# R4_Odzyskowa.net
KiCad netlist of a schematic drawn in EasyEDA
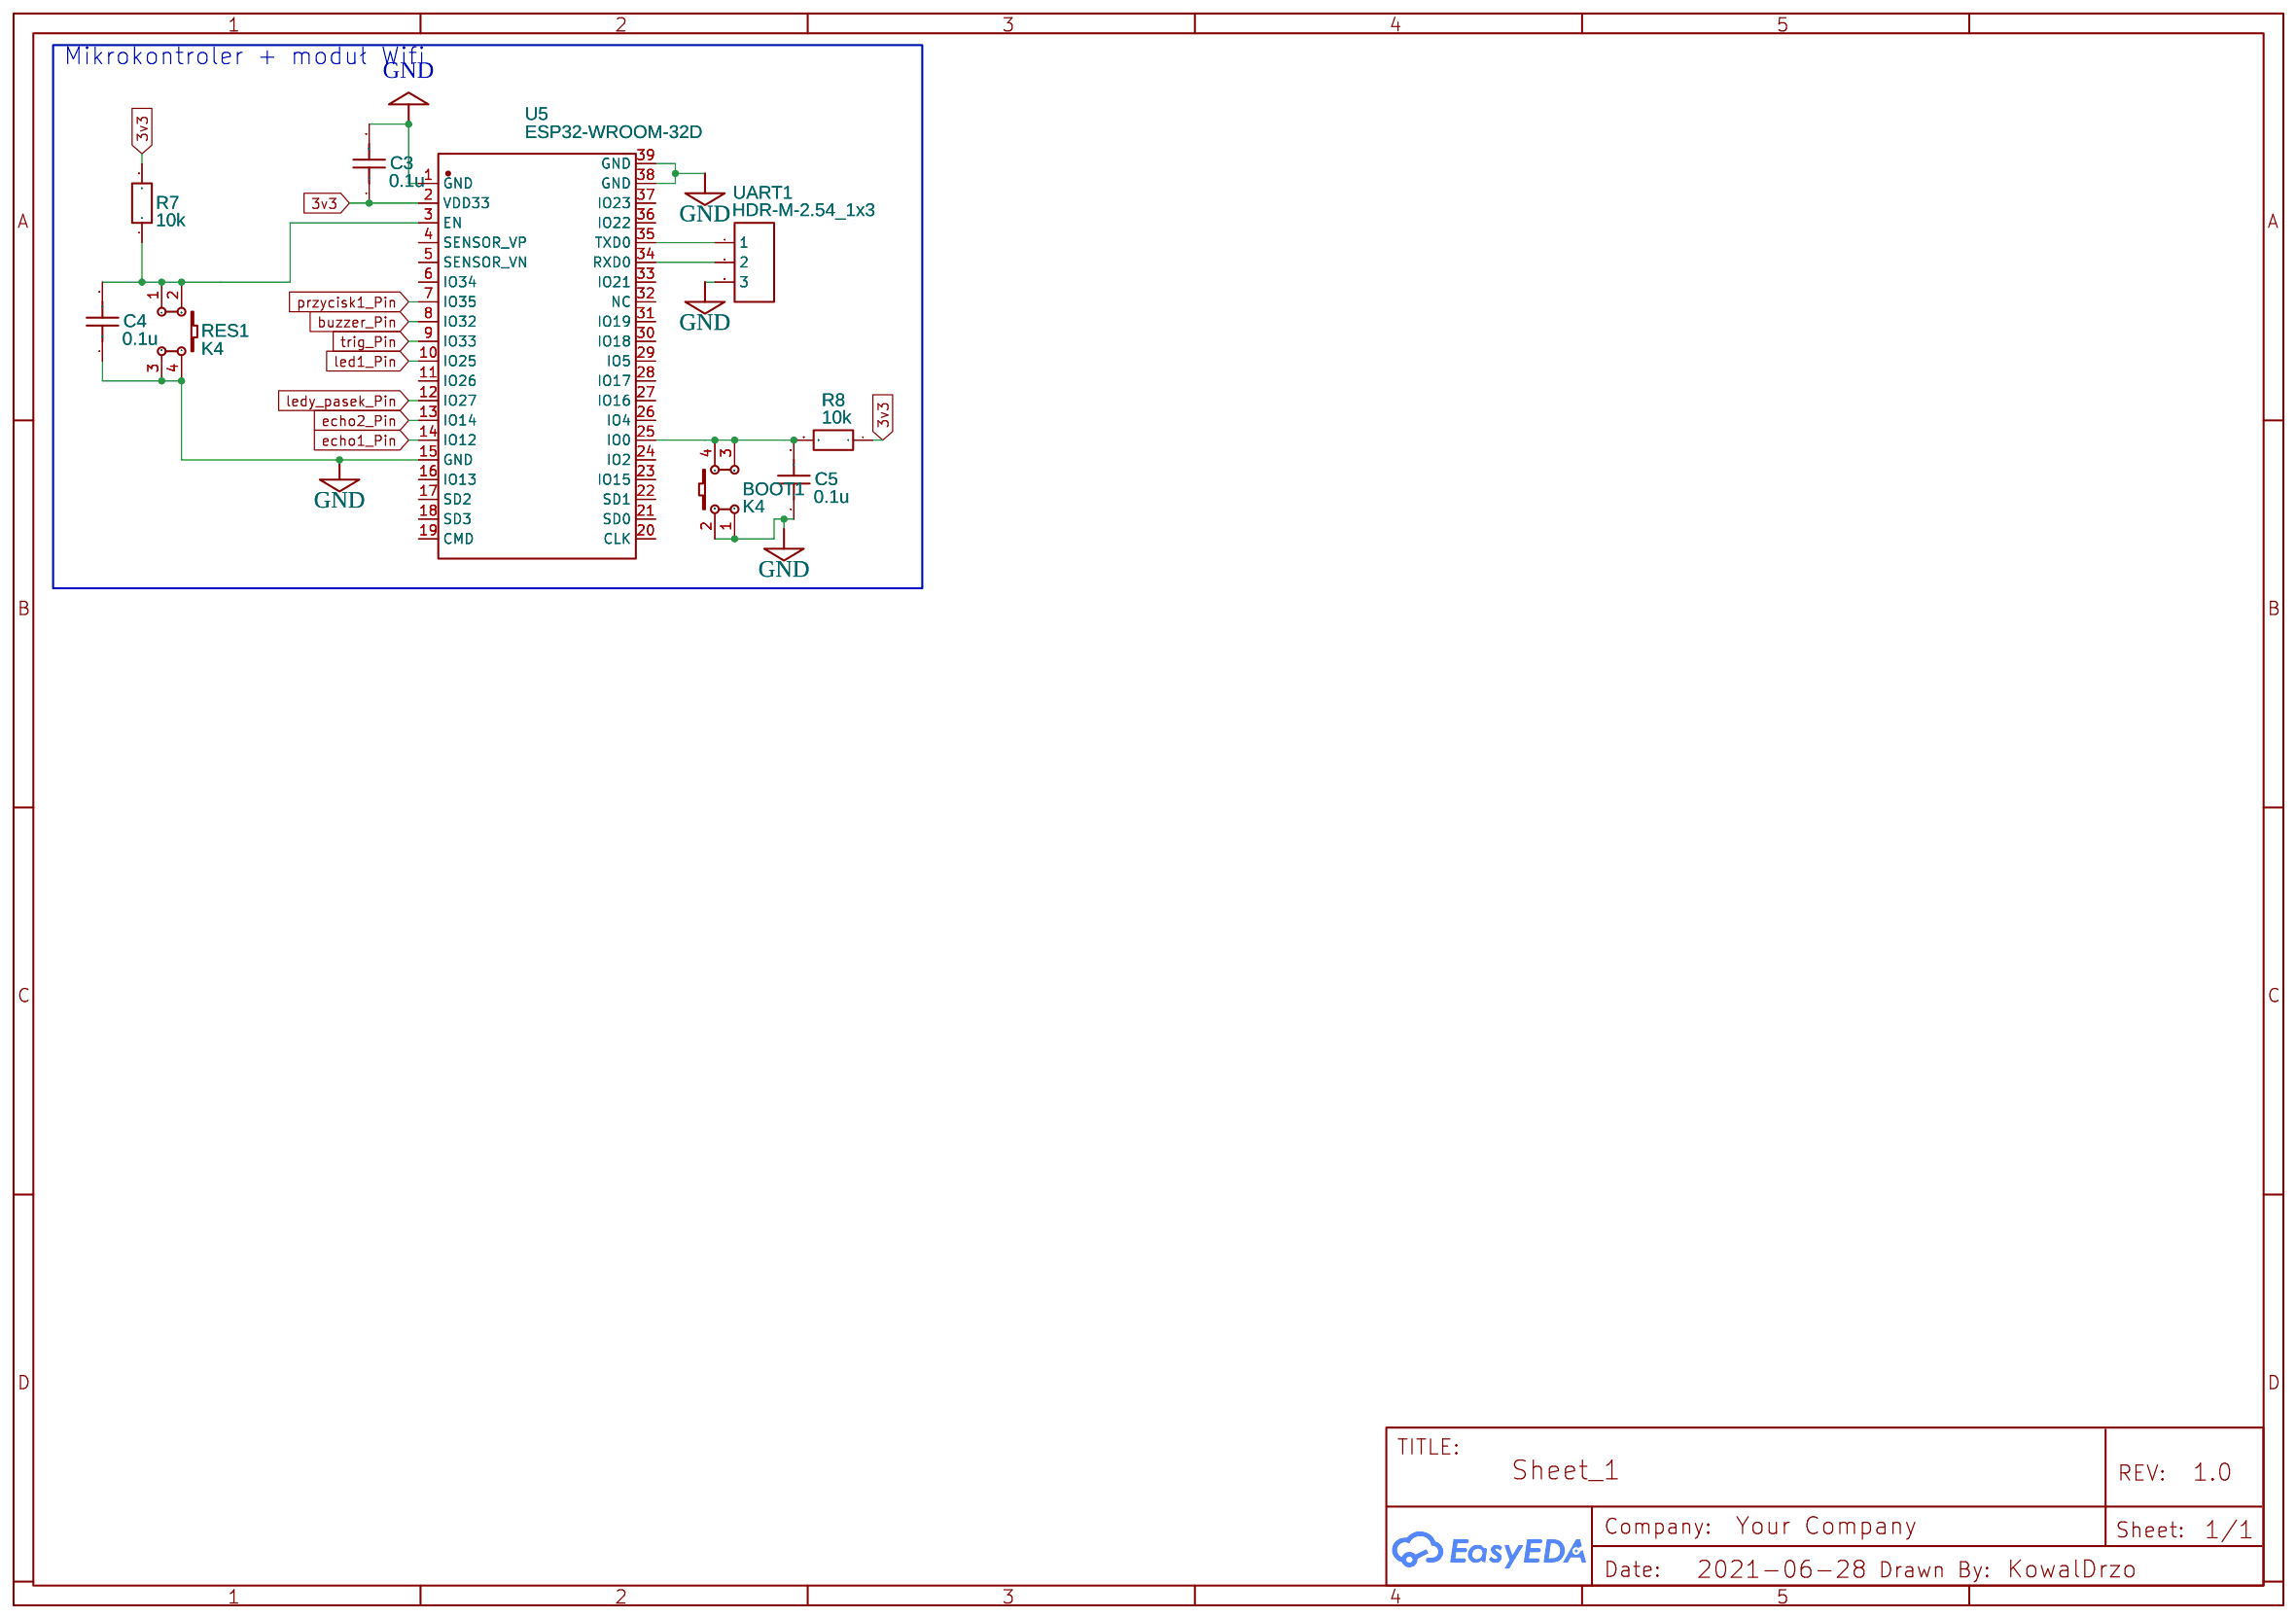
[diagram p0: schematic sheet]

(export (version "E")
  (design (tool "Eeschema 10.0.6"))
  (components
    (comp (ref "BOOT1")
      (value "K4")
      (fields
        (field (name "BOM_Manufacturer Part") "K2-1102DP-E4SW-04")
        (field (name "BOM_Supplier Part") "C136684")
      )
      (libsource (lib "") (part "K4-6×6_TH"))
    )
    (comp (ref "C3") (value "0.1u") (libsource (lib "") (part "C_0805_US")))
    (comp (ref "C4") (value "0.1u") (libsource (lib "") (part "C_0805_US")))
    (comp (ref "C5") (value "0.1u") (libsource (lib "") (part "C_0805_US")))
    (comp (ref "R7") (value "10k") (libsource (lib "") (part "R_0805_EU")))
    (comp (ref "R8") (value "10k") (libsource (lib "") (part "R_0805_EU_1")))
    (comp (ref "RES1")
      (value "K4")
      (fields
        (field (name "BOM_Manufacturer Part") "K2-1102DP-E4SW-04")
        (field (name "BOM_Supplier Part") "C136684")
      )
      (libsource (lib "") (part "K4-6×6_TH_1"))
    )
    (comp (ref "U5")
      (value "ESP32-WROOM-32D")
      (fields (field (name "BOM_Supplier Part") "C473012"))
      (libsource (lib "") (part "ESP32-WROOM-32D"))
    )
    (comp (ref "UART1")
      (value "HDR-M-2.54_1x3")
      (fields (field (name "BOM_Supplier Part") "C180248"))
      (libsource (lib "") (part "HDR-M-2.54_1x3"))
    )
  )
  (nets
    (net (code "1") (name "3v3") (class "Default")
      (node (ref "C3") (pin "1") (pinfunction "1_1") (pintype "unspecified"))
      (node (ref "R7") (pin "2") (pinfunction "2_2") (pintype "unspecified"))
      (node (ref "R8") (pin "1") (pinfunction "1_1") (pintype "unspecified"))
      (node (ref "U5") (pin "2") (pinfunction "VDD33_2") (pintype "unspecified"))
    )
    (net (code "2") (name "GND") (class "Default")
      (node (ref "BOOT1") (pin "1") (pinfunction "1_1") (pintype "unspecified"))
      (node (ref "BOOT1") (pin "2") (pinfunction "2_2") (pintype "unspecified"))
      (node (ref "C3") (pin "2") (pinfunction "2_2") (pintype "unspecified"))
      (node (ref "C4") (pin "1") (pinfunction "1_1") (pintype "unspecified"))
      (node (ref "C5") (pin "1") (pinfunction "1_1") (pintype "unspecified"))
      (node (ref "RES1") (pin "3") (pinfunction "3_3") (pintype "unspecified"))
      (node (ref "RES1") (pin "4") (pinfunction "4_4") (pintype "unspecified"))
      (node (ref "U5") (pin "1") (pinfunction "GND_1") (pintype "unspecified"))
      (node (ref "U5") (pin "15") (pinfunction "GND_15") (pintype "unspecified"))
      (node (ref "U5") (pin "38") (pinfunction "GND_38") (pintype "unspecified"))
      (node (ref "U5") (pin "39") (pinfunction "GND_39") (pintype "unspecified"))
      (node (ref "UART1") (pin "3") (pinfunction "3_3") (pintype "input"))
    )
    (net (code "3") (name "Net-(U5-EN)") (class "Default")
      (node (ref "C4") (pin "2") (pinfunction "2_2") (pintype "unspecified"))
      (node (ref "R7") (pin "1") (pinfunction "1_1") (pintype "unspecified"))
      (node (ref "RES1") (pin "1") (pinfunction "1_1") (pintype "unspecified"))
      (node (ref "RES1") (pin "2") (pinfunction "2_2") (pintype "unspecified"))
      (node (ref "U5") (pin "3") (pinfunction "EN_3") (pintype "unspecified"))
    )
    (net (code "4") (name "Net-(U5-IO0)") (class "Default")
      (node (ref "BOOT1") (pin "3") (pinfunction "3_3") (pintype "unspecified"))
      (node (ref "BOOT1") (pin "4") (pinfunction "4_4") (pintype "unspecified"))
      (node (ref "C5") (pin "2") (pinfunction "2_2") (pintype "unspecified"))
      (node (ref "R8") (pin "2") (pinfunction "2_2") (pintype "unspecified"))
      (node (ref "U5") (pin "25") (pinfunction "IO0_25") (pintype "unspecified"))
    )
    (net (code "5") (name "Net-(U5-RXD0)") (class "Default")
      (node (ref "U5") (pin "34") (pinfunction "RXD0_34") (pintype "unspecified"))
      (node (ref "UART1") (pin "2") (pinfunction "2_2") (pintype "input"))
    )
    (net (code "6") (name "Net-(U5-TXD0)") (class "Default")
      (node (ref "U5") (pin "35") (pinfunction "TXD0_35") (pintype "unspecified"))
      (node (ref "UART1") (pin "1") (pinfunction "1_1") (pintype "input"))
    )
    (net (code "7") (name "buzzer_Pin") (class "Default")
      (node (ref "U5") (pin "8") (pinfunction "IO32_8") (pintype "unspecified"))
    )
    (net (code "8") (name "echo1_Pin") (class "Default")
      (node (ref "U5") (pin "14") (pinfunction "IO12_14") (pintype "unspecified"))
    )
    (net (code "9") (name "echo2_Pin") (class "Default")
      (node (ref "U5") (pin "13") (pinfunction "IO14_13") (pintype "unspecified"))
    )
    (net (code "10") (name "led1_Pin") (class "Default")
      (node (ref "U5") (pin "10") (pinfunction "IO25_10") (pintype "unspecified"))
    )
    (net (code "11") (name "ledy_pasek_Pin") (class "Default")
      (node (ref "U5") (pin "12") (pinfunction "IO27_12") (pintype "unspecified"))
    )
    (net (code "12") (name "przycisk1_Pin") (class "Default")
      (node (ref "U5") (pin "7") (pinfunction "IO35_7") (pintype "unspecified"))
    )
    (net (code "13") (name "trig_Pin") (class "Default")
      (node (ref "U5") (pin "9") (pinfunction "IO33_9") (pintype "unspecified"))
    )
    (net (code "14") (name "unconnected-(U5-CLK-Pad20)") (class "Default")
      (node (ref "U5") (pin "20") (pinfunction "CLK_20") (pintype "unspecified"))
    )
    (net (code "15") (name "unconnected-(U5-CMD-Pad19)") (class "Default")
      (node (ref "U5") (pin "19") (pinfunction "CMD_19") (pintype "unspecified"))
    )
    (net (code "16") (name "unconnected-(U5-IO2-Pad24)") (class "Default")
      (node (ref "U5") (pin "24") (pinfunction "IO2_24") (pintype "unspecified"))
    )
    (net (code "17") (name "unconnected-(U5-IO4-Pad26)") (class "Default")
      (node (ref "U5") (pin "26") (pinfunction "IO4_26") (pintype "unspecified"))
    )
    (net (code "18") (name "unconnected-(U5-IO5-Pad29)") (class "Default")
      (node (ref "U5") (pin "29") (pinfunction "IO5_29") (pintype "unspecified"))
    )
    (net (code "19") (name "unconnected-(U5-IO13-Pad16)") (class "Default")
      (node (ref "U5") (pin "16") (pinfunction "IO13_16") (pintype "unspecified"))
    )
    (net (code "20") (name "unconnected-(U5-IO15-Pad23)") (class "Default")
      (node (ref "U5") (pin "23") (pinfunction "IO15_23") (pintype "unspecified"))
    )
    (net (code "21") (name "unconnected-(U5-IO16-Pad27)") (class "Default")
      (node (ref "U5") (pin "27") (pinfunction "IO16_27") (pintype "unspecified"))
    )
    (net (code "22") (name "unconnected-(U5-IO17-Pad28)") (class "Default")
      (node (ref "U5") (pin "28") (pinfunction "IO17_28") (pintype "unspecified"))
    )
    (net (code "23") (name "unconnected-(U5-IO18-Pad30)") (class "Default")
      (node (ref "U5") (pin "30") (pinfunction "IO18_30") (pintype "unspecified"))
    )
    (net (code "24") (name "unconnected-(U5-IO19-Pad31)") (class "Default")
      (node (ref "U5") (pin "31") (pinfunction "IO19_31") (pintype "unspecified"))
    )
    (net (code "25") (name "unconnected-(U5-IO21-Pad33)") (class "Default")
      (node (ref "U5") (pin "33") (pinfunction "IO21_33") (pintype "unspecified"))
    )
    (net (code "26") (name "unconnected-(U5-IO22-Pad36)") (class "Default")
      (node (ref "U5") (pin "36") (pinfunction "IO22_36") (pintype "unspecified"))
    )
    (net (code "27") (name "unconnected-(U5-IO23-Pad37)") (class "Default")
      (node (ref "U5") (pin "37") (pinfunction "IO23_37") (pintype "unspecified"))
    )
    (net (code "28") (name "unconnected-(U5-IO26-Pad11)") (class "Default")
      (node (ref "U5") (pin "11") (pinfunction "IO26_11") (pintype "unspecified"))
    )
    (net (code "29") (name "unconnected-(U5-IO34-Pad6)") (class "Default")
      (node (ref "U5") (pin "6") (pinfunction "IO34_6") (pintype "unspecified"))
    )
    (net (code "30") (name "unconnected-(U5-NC-Pad32)") (class "Default")
      (node (ref "U5") (pin "32") (pinfunction "NC_32") (pintype "unspecified"))
    )
    (net (code "31") (name "unconnected-(U5-SD0-Pad21)") (class "Default")
      (node (ref "U5") (pin "21") (pinfunction "SD0_21") (pintype "unspecified"))
    )
    (net (code "32") (name "unconnected-(U5-SD1-Pad22)") (class "Default")
      (node (ref "U5") (pin "22") (pinfunction "SD1_22") (pintype "unspecified"))
    )
    (net (code "33") (name "unconnected-(U5-SD2-Pad17)") (class "Default")
      (node (ref "U5") (pin "17") (pinfunction "SD2_17") (pintype "unspecified"))
    )
    (net (code "34") (name "unconnected-(U5-SD3-Pad18)") (class "Default")
      (node (ref "U5") (pin "18") (pinfunction "SD3_18") (pintype "unspecified"))
    )
    (net (code "35") (name "unconnected-(U5-SENSOR_VN-Pad5)") (class "Default")
      (node (ref "U5") (pin "5") (pinfunction "SENSOR_VN_5") (pintype "unspecified"))
    )
    (net (code "36") (name "unconnected-(U5-SENSOR_VP-Pad4)") (class "Default")
      (node (ref "U5") (pin "4") (pinfunction "SENSOR_VP_4") (pintype "unspecified"))
    )
  )
)
